# PCB.net
KiCad netlist of a schematic drawn in Altium Designer
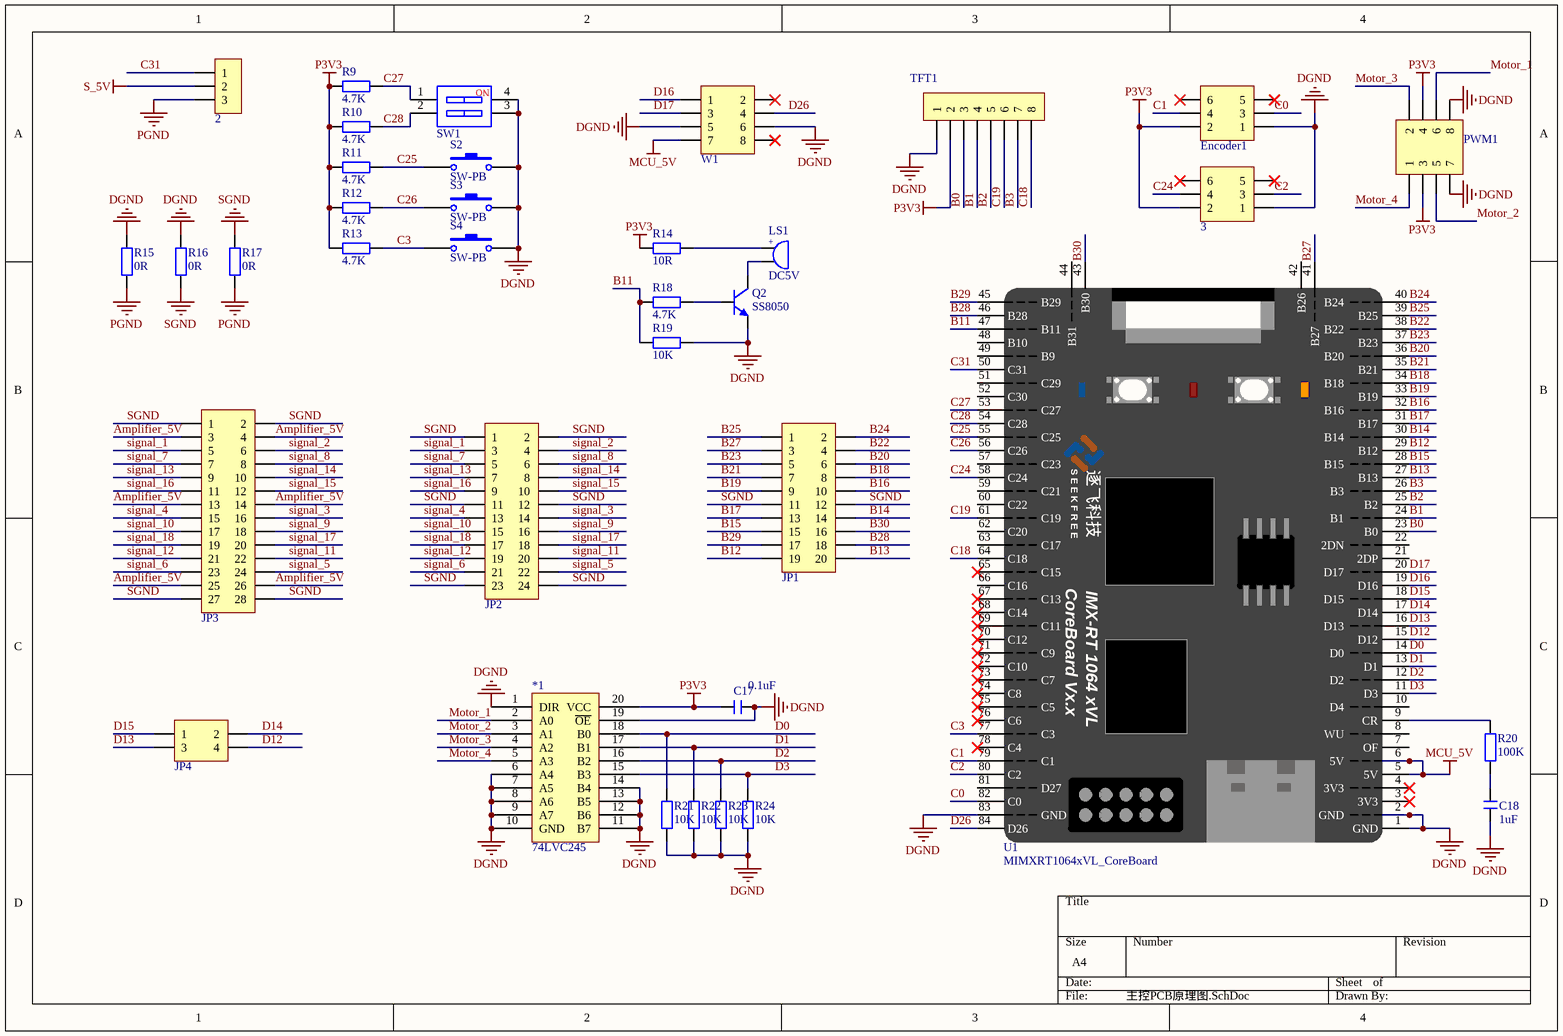
[diagram p0: 主控PCB原理图.SchDoc]

(export (version "E")
  (design (tool "Eeschema 10.0.6"))
  (components
    (comp (ref "*1")
      (value "74LVC245")
      (footprint "TSSOP20_M")
      (libsource (lib "主控PCB原理图库") (part "74LVC245"))
    )
    (comp (ref "2")
      (value "HDR-1X3")
      (footprint "HDR2.54-LI-3P")
      (description "3P接插件")
      (libsource (lib "5.4 - 接插件-脚距2.54 (100mil) ") (part "Header 3"))
    )
    (comp (ref "3")
      (value "Header3X2")
      (footprint "HDR2.54-LI-2x3P")
      (description "3*2P接插件")
      (libsource (lib "5.4 - 接插件-脚距2.54 (100mil) ") (part "Header 3X2"))
    )
    (comp (ref "C17")
      (value "0.1uF")
      (footprint "C 0603_L")
      (description "贴片电容")
      (libsource (lib "0.1 - 电阻-电容-电感") (part "C"))
    )
    (comp (ref "C18")
      (value "1uF")
      (footprint "C 0603_L")
      (description "贴片电容")
      (libsource (lib "0.1 - 电阻-电容-电感") (part "C"))
    )
    (comp (ref "Encoder1")
      (value "Header3X2")
      (footprint "HDR2.54-LI-2x3P")
      (description "3*2P接插件")
      (libsource (lib "5.4 - 接插件-脚距2.54 (100mil) ") (part "Header 3X2"))
    )
    (comp (ref "JP1")
      (value "Header 2X10")
      (footprint "HDR2.54-M-LS-2x10P")
      (description "10*2P接插件")
      (libsource (lib "5.4 - 接插件-脚距2.54 (100mil) ") (part "Header 10X2"))
    )
    (comp (ref "JP2")
      (value "Header 2X11")
      (footprint "HDR2.54-LI-2x12P")
      (description "12*2P接插件")
      (libsource (lib "5.4 - 接插件-脚距2.54 (100mil) ") (part "Header 12X2"))
    )
    (comp (ref "JP3")
      (value "Header 2X11")
      (footprint "HDR2.54-M-LS-2x14P")
      (description "14*2P接插件")
      (libsource (lib "5.4 - 接插件-脚距2.54 (100mil) ") (part "Header 14X2"))
    )
    (comp (ref "JP4")
      (value "Header2X2")
      (footprint "HDR2.54-LI-2x2P")
      (description "2*2P接插件")
      (libsource (lib "5.4 - 接插件-脚距2.54 (100mil) ") (part "Header 2X2"))
    )
    (comp (ref "LS1")
      (value "DC5V")
      (footprint "BEEP 7.6X12X9.5")
      (description "蜂鸣器")
      (libsource (lib "0.7 - 常用按键-开关-蜂鸣器-电池") (part "BEEP"))
    )
    (comp (ref "PWM1")
      (value "Header 4X2")
      (footprint "HDR2.54-LI-2x4P")
      (description "4*2P接插件")
      (libsource (lib "") (part "Header 4X2_1"))
    )
    (comp (ref "Q2")
      (value "SS8050")
      (footprint "SOT23-3N")
      (description "高频放大-NPN型")
      (libsource (lib "0.4 - 三极管-场效应管-可控硅") (part "8050-SMD"))
    )
    (comp (ref "R9")
      (value "4.7K")
      (footprint "R 0603_L")
      (description "贴片电阻")
      (libsource (lib "0.1 - 电阻-电容-电感") (part "R"))
    )
    (comp (ref "R10")
      (value "4.7K")
      (footprint "R 0603_L")
      (description "贴片电阻")
      (libsource (lib "0.1 - 电阻-电容-电感") (part "R"))
    )
    (comp (ref "R11")
      (value "4.7K")
      (footprint "R 0603_L")
      (description "贴片电阻")
      (libsource (lib "0.1 - 电阻-电容-电感") (part "R"))
    )
    (comp (ref "R12")
      (value "4.7K")
      (footprint "R 0603_L")
      (description "贴片电阻")
      (libsource (lib "0.1 - 电阻-电容-电感") (part "R"))
    )
    (comp (ref "R13")
      (value "4.7K")
      (footprint "R 0603_L")
      (description "贴片电阻")
      (libsource (lib "0.1 - 电阻-电容-电感") (part "R"))
    )
    (comp (ref "R14")
      (value "10R")
      (footprint "R 0603_L")
      (description "贴片电阻")
      (libsource (lib "0.1 - 电阻-电容-电感") (part "R"))
    )
    (comp (ref "R15")
      (value "0R")
      (footprint "R 0603_L")
      (description "贴片电阻")
      (libsource (lib "0.1 - 电阻-电容-电感") (part "R"))
    )
    (comp (ref "R16")
      (value "0R")
      (footprint "R 0603_L")
      (description "贴片电阻")
      (libsource (lib "0.1 - 电阻-电容-电感") (part "R"))
    )
    (comp (ref "R17")
      (value "0R")
      (footprint "R 0603_L")
      (description "贴片电阻")
      (libsource (lib "0.1 - 电阻-电容-电感") (part "R"))
    )
    (comp (ref "R18")
      (value "4.7K")
      (footprint "R 0603_L")
      (description "贴片电阻")
      (libsource (lib "0.1 - 电阻-电容-电感") (part "R"))
    )
    (comp (ref "R19")
      (value "10K")
      (footprint "R 0603_L")
      (description "贴片电阻")
      (libsource (lib "0.1 - 电阻-电容-电感") (part "R"))
    )
    (comp (ref "R20")
      (value "100K")
      (footprint "R 0603_L")
      (description "贴片电阻")
      (libsource (lib "0.1 - 电阻-电容-电感") (part "R"))
    )
    (comp (ref "R21")
      (value "10K")
      (footprint "R 0603_L")
      (description "贴片电阻")
      (libsource (lib "0.1 - 电阻-电容-电感") (part "R"))
    )
    (comp (ref "R22")
      (value "10K")
      (footprint "R 0603_L")
      (description "贴片电阻")
      (libsource (lib "0.1 - 电阻-电容-电感") (part "R"))
    )
    (comp (ref "R23")
      (value "10K")
      (footprint "R 0603_L")
      (description "贴片电阻")
      (libsource (lib "0.1 - 电阻-电容-电感") (part "R"))
    )
    (comp (ref "R24")
      (value "10K")
      (footprint "R 0603_L")
      (description "贴片电阻")
      (libsource (lib "0.1 - 电阻-电容-电感") (part "R"))
    )
    (comp (ref "S2")
      (value "SW-PB")
      (footprint "TSW SMD-3*6*4.3")
      (description "微动开关")
      (libsource (lib "0.7 - 常用按键-开关-蜂鸣器-电池") (part "SW-PB"))
    )
    (comp (ref "S3")
      (value "SW-PB")
      (footprint "TSW SMD-3*6*4.3")
      (description "微动开关")
      (libsource (lib "0.7 - 常用按键-开关-蜂鸣器-电池") (part "SW-PB"))
    )
    (comp (ref "S4")
      (value "SW-PB")
      (footprint "TSW SMD-3*6*4.3")
      (description "微动开关")
      (libsource (lib "0.7 - 常用按键-开关-蜂鸣器-电池") (part "SW-PB"))
    )
    (comp (ref "SW1")
      (value "SW-2P")
      (footprint "CSW DIP-2P_G")
      (description "2路编码开关")
      (libsource (lib "0.7 - 常用按键-开关-蜂鸣器-电池") (part "SW-2P"))
    )
    (comp (ref "TFT1")
      (value "HDR-1X8")
      (footprint "HDR2.54-LI-8P")
      (description "8P接插件")
      (libsource (lib "5.4 - 接插件-脚距2.54 (100mil) ") (part "Header 8"))
    )
    (comp (ref "U1")
      (value "MIMXRT1064xVL_CoreBoard")
      (footprint "MIMXRT1064xVL_CoreBoard")
      (description "逐飞科技i.MX RT1064核心板整体原理，可直接使用")
      (libsource (lib "RT1064 V1.2核心板原理库") (part "MIMXRT1064xVL_CoreBoard"))
    )
    (comp (ref "W1")
      (value "Header 4X2")
      (footprint "HDR2.54-M-LS-2x4P")
      (description "4*2P接插件")
      (libsource (lib "5.4 - 接插件-脚距2.54 (100mil) ") (part "Header 4X2"))
    )
  )
  (nets
    (net (code "1") (name "/Amplifier_5V") (class "Default")
      (node (ref "JP3") (pin "13") (pinfunction "13_13") (pintype "passive"))
      (node (ref "JP3") (pin "14") (pinfunction "14_14") (pintype "passive"))
      (node (ref "JP3") (pin "25") (pinfunction "25_25") (pintype "passive"))
      (node (ref "JP3") (pin "26") (pinfunction "26_26") (pintype "passive"))
      (node (ref "JP3") (pin "3") (pinfunction "3_3") (pintype "passive"))
      (node (ref "JP3") (pin "4") (pinfunction "4_4") (pintype "passive"))
    )
    (net (code "2") (name "/B0") (class "Default")
      (node (ref "TFT1") (pin "3") (pinfunction "3_3") (pintype "passive"))
      (node (ref "U1") (pin "23") (pinfunction "B0_23") (pintype "passive"))
    )
    (net (code "3") (name "/B1") (class "Default")
      (node (ref "TFT1") (pin "4") (pinfunction "4_4") (pintype "passive"))
      (node (ref "U1") (pin "24") (pinfunction "B1_24") (pintype "passive"))
    )
    (net (code "4") (name "/B2") (class "Default")
      (node (ref "TFT1") (pin "5") (pinfunction "5_5") (pintype "passive"))
      (node (ref "U1") (pin "25") (pinfunction "B2_25") (pintype "passive"))
    )
    (net (code "5") (name "/B3") (class "Default")
      (node (ref "TFT1") (pin "7") (pinfunction "7_7") (pintype "passive"))
      (node (ref "U1") (pin "26") (pinfunction "B3_26") (pintype "passive"))
    )
    (net (code "6") (name "/B11") (class "Default")
      (node (ref "R18") (pin "1") (pinfunction "1_1") (pintype "passive"))
      (node (ref "R19") (pin "1") (pinfunction "1_1") (pintype "passive"))
      (node (ref "U1") (pin "47") (pinfunction "B11_47") (pintype "passive"))
    )
    (net (code "7") (name "/B12") (class "Default")
      (node (ref "JP1") (pin "19") (pinfunction "19_19") (pintype "passive"))
      (node (ref "U1") (pin "29") (pinfunction "B12_29") (pintype "passive"))
    )
    (net (code "8") (name "/B13") (class "Default")
      (node (ref "JP1") (pin "20") (pinfunction "20_20") (pintype "passive"))
      (node (ref "U1") (pin "27") (pinfunction "B13_27") (pintype "passive"))
    )
    (net (code "9") (name "/B14") (class "Default")
      (node (ref "JP1") (pin "14") (pinfunction "14_14") (pintype "passive"))
      (node (ref "U1") (pin "30") (pinfunction "B14_30") (pintype "passive"))
    )
    (net (code "10") (name "/B15") (class "Default")
      (node (ref "JP1") (pin "15") (pinfunction "15_15") (pintype "passive"))
      (node (ref "U1") (pin "28") (pinfunction "B15_28") (pintype "passive"))
    )
    (net (code "11") (name "/B16") (class "Default")
      (node (ref "JP1") (pin "10") (pinfunction "10_10") (pintype "passive"))
      (node (ref "U1") (pin "32") (pinfunction "B16_32") (pintype "passive"))
    )
    (net (code "12") (name "/B17") (class "Default")
      (node (ref "JP1") (pin "13") (pinfunction "13_13") (pintype "passive"))
      (node (ref "U1") (pin "31") (pinfunction "B17_31") (pintype "passive"))
    )
    (net (code "13") (name "/B18") (class "Default")
      (node (ref "JP1") (pin "8") (pinfunction "8_8") (pintype "passive"))
      (node (ref "U1") (pin "34") (pinfunction "B18_34") (pintype "passive"))
    )
    (net (code "14") (name "/B19") (class "Default")
      (node (ref "JP1") (pin "9") (pinfunction "9_9") (pintype "passive"))
      (node (ref "U1") (pin "33") (pinfunction "B19_33") (pintype "passive"))
    )
    (net (code "15") (name "/B20") (class "Default")
      (node (ref "JP1") (pin "6") (pinfunction "6_6") (pintype "passive"))
      (node (ref "U1") (pin "36") (pinfunction "B20_36") (pintype "passive"))
    )
    (net (code "16") (name "/B21") (class "Default")
      (node (ref "JP1") (pin "7") (pinfunction "7_7") (pintype "passive"))
      (node (ref "U1") (pin "35") (pinfunction "B21_35") (pintype "passive"))
    )
    (net (code "17") (name "/B22") (class "Default")
      (node (ref "JP1") (pin "4") (pinfunction "4_4") (pintype "passive"))
      (node (ref "U1") (pin "38") (pinfunction "B22_38") (pintype "passive"))
    )
    (net (code "18") (name "/B23") (class "Default")
      (node (ref "JP1") (pin "5") (pinfunction "5_5") (pintype "passive"))
      (node (ref "U1") (pin "37") (pinfunction "B23_37") (pintype "passive"))
    )
    (net (code "19") (name "/B24") (class "Default")
      (node (ref "JP1") (pin "2") (pinfunction "2_2") (pintype "passive"))
      (node (ref "U1") (pin "40") (pinfunction "B24_40") (pintype "passive"))
    )
    (net (code "20") (name "/B25") (class "Default")
      (node (ref "JP1") (pin "1") (pinfunction "1_1") (pintype "passive"))
      (node (ref "U1") (pin "39") (pinfunction "B25_39") (pintype "passive"))
    )
    (net (code "21") (name "/B27") (class "Default")
      (node (ref "JP1") (pin "3") (pinfunction "3_3") (pintype "passive"))
      (node (ref "U1") (pin "41") (pinfunction "B27_41") (pintype "passive"))
    )
    (net (code "22") (name "/B28") (class "Default")
      (node (ref "JP1") (pin "18") (pinfunction "18_18") (pintype "passive"))
      (node (ref "U1") (pin "46") (pinfunction "B28_46") (pintype "passive"))
    )
    (net (code "23") (name "/B29") (class "Default")
      (node (ref "JP1") (pin "17") (pinfunction "17_17") (pintype "passive"))
      (node (ref "U1") (pin "45") (pinfunction "B29_45") (pintype "passive"))
    )
    (net (code "24") (name "/B30") (class "Default")
      (node (ref "JP1") (pin "16") (pinfunction "16_16") (pintype "passive"))
      (node (ref "U1") (pin "43") (pinfunction "B30_43") (pintype "passive"))
    )
    (net (code "25") (name "/C0") (class "Default")
      (node (ref "Encoder1") (pin "3") (pinfunction "3_3") (pintype "passive"))
      (node (ref "U1") (pin "82") (pinfunction "C0_82") (pintype "passive"))
    )
    (net (code "26") (name "/C1") (class "Default")
      (node (ref "Encoder1") (pin "4") (pinfunction "4_4") (pintype "passive"))
      (node (ref "U1") (pin "79") (pinfunction "C1_79") (pintype "passive"))
    )
    (net (code "27") (name "/C2") (class "Default")
      (node (ref "3") (pin "3") (pinfunction "3_3") (pintype "passive"))
      (node (ref "U1") (pin "80") (pinfunction "C2_80") (pintype "passive"))
    )
    (net (code "28") (name "/C3") (class "Default")
      (node (ref "R13") (pin "2") (pinfunction "2_2") (pintype "passive"))
      (node (ref "S4") (pin "1") (pinfunction "1_1") (pintype "passive"))
      (node (ref "U1") (pin "77") (pinfunction "C3_77") (pintype "passive"))
    )
    (net (code "29") (name "/C18") (class "Default")
      (node (ref "TFT1") (pin "8") (pinfunction "8_8") (pintype "passive"))
      (node (ref "U1") (pin "64") (pinfunction "C18_64") (pintype "passive"))
    )
    (net (code "30") (name "/C19") (class "Default")
      (node (ref "TFT1") (pin "6") (pinfunction "6_6") (pintype "passive"))
      (node (ref "U1") (pin "61") (pinfunction "C19_61") (pintype "passive"))
    )
    (net (code "31") (name "/C24") (class "Default")
      (node (ref "3") (pin "4") (pinfunction "4_4") (pintype "passive"))
      (node (ref "U1") (pin "58") (pinfunction "C24_58") (pintype "passive"))
    )
    (net (code "32") (name "/C25") (class "Default")
      (node (ref "R11") (pin "2") (pinfunction "2_2") (pintype "passive"))
      (node (ref "S2") (pin "1") (pinfunction "1_1") (pintype "passive"))
      (node (ref "U1") (pin "55") (pinfunction "C25_55") (pintype "passive"))
    )
    (net (code "33") (name "/C26") (class "Default")
      (node (ref "R12") (pin "2") (pinfunction "2_2") (pintype "passive"))
      (node (ref "S3") (pin "1") (pinfunction "1_1") (pintype "passive"))
      (node (ref "U1") (pin "56") (pinfunction "C26_56") (pintype "passive"))
    )
    (net (code "34") (name "/C27") (class "Default")
      (node (ref "R9") (pin "2") (pinfunction "2_2") (pintype "passive"))
      (node (ref "SW1") (pin "1") (pinfunction "1_1") (pintype "passive"))
      (node (ref "U1") (pin "53") (pinfunction "C27_53") (pintype "passive"))
    )
    (net (code "35") (name "/C28") (class "Default")
      (node (ref "R10") (pin "2") (pinfunction "2_2") (pintype "passive"))
      (node (ref "SW1") (pin "2") (pinfunction "2_2") (pintype "passive"))
      (node (ref "U1") (pin "54") (pinfunction "C28_54") (pintype "passive"))
    )
    (net (code "36") (name "/C31") (class "Default")
      (node (ref "2") (pin "1") (pinfunction "1_1") (pintype "passive"))
      (node (ref "U1") (pin "50") (pinfunction "C31_50") (pintype "passive"))
    )
    (net (code "37") (name "/D0") (class "Default")
      (node (ref "*1") (pin "18") (pinfunction "B0_18") (pintype "passive"))
      (node (ref "R21") (pin "2") (pinfunction "2_2") (pintype "passive"))
      (node (ref "U1") (pin "14") (pinfunction "D0_14") (pintype "passive"))
    )
    (net (code "38") (name "/D1") (class "Default")
      (node (ref "*1") (pin "17") (pinfunction "B1_17") (pintype "passive"))
      (node (ref "R22") (pin "2") (pinfunction "2_2") (pintype "passive"))
      (node (ref "U1") (pin "13") (pinfunction "D1_13") (pintype "passive"))
    )
    (net (code "39") (name "/D2") (class "Default")
      (node (ref "*1") (pin "16") (pinfunction "B2_16") (pintype "passive"))
      (node (ref "R23") (pin "2") (pinfunction "2_2") (pintype "passive"))
      (node (ref "U1") (pin "12") (pinfunction "D2_12") (pintype "passive"))
    )
    (net (code "40") (name "/D3") (class "Default")
      (node (ref "*1") (pin "15") (pinfunction "B3_15") (pintype "passive"))
      (node (ref "R24") (pin "2") (pinfunction "2_2") (pintype "passive"))
      (node (ref "U1") (pin "11") (pinfunction "D3_11") (pintype "passive"))
    )
    (net (code "41") (name "/D12") (class "Default")
      (node (ref "JP4") (pin "4") (pinfunction "4_4") (pintype "passive"))
      (node (ref "U1") (pin "15") (pinfunction "D12_15") (pintype "passive"))
    )
    (net (code "42") (name "/D13") (class "Default")
      (node (ref "JP4") (pin "3") (pinfunction "3_3") (pintype "passive"))
      (node (ref "U1") (pin "16") (pinfunction "D13_16") (pintype "passive"))
    )
    (net (code "43") (name "/D14") (class "Default")
      (node (ref "JP4") (pin "2") (pinfunction "2_2") (pintype "passive"))
      (node (ref "U1") (pin "17") (pinfunction "D14_17") (pintype "passive"))
    )
    (net (code "44") (name "/D15") (class "Default")
      (node (ref "JP4") (pin "1") (pinfunction "1_1") (pintype "passive"))
      (node (ref "U1") (pin "18") (pinfunction "D15_18") (pintype "passive"))
    )
    (net (code "45") (name "/D16") (class "Default")
      (node (ref "U1") (pin "19") (pinfunction "D16_19") (pintype "passive"))
      (node (ref "W1") (pin "1") (pinfunction "1_1") (pintype "passive"))
    )
    (net (code "46") (name "/D17") (class "Default")
      (node (ref "U1") (pin "20") (pinfunction "D17_20") (pintype "passive"))
      (node (ref "W1") (pin "3") (pinfunction "3_3") (pintype "passive"))
    )
    (net (code "47") (name "/D26") (class "Default")
      (node (ref "U1") (pin "84") (pinfunction "D26_84") (pintype "passive"))
      (node (ref "W1") (pin "4") (pinfunction "4_4") (pintype "passive"))
    )
    (net (code "48") (name "/Motor_1") (class "Default")
      (node (ref "*1") (pin "2") (pinfunction "A0_2") (pintype "passive"))
      (node (ref "PWM1") (pin "6") (pinfunction "6_6") (pintype "passive"))
    )
    (net (code "49") (name "/Motor_2") (class "Default")
      (node (ref "*1") (pin "3") (pinfunction "A1_3") (pintype "passive"))
      (node (ref "PWM1") (pin "5") (pinfunction "5_5") (pintype "passive"))
    )
    (net (code "50") (name "/Motor_3") (class "Default")
      (node (ref "*1") (pin "4") (pinfunction "A2_4") (pintype "passive"))
      (node (ref "PWM1") (pin "2") (pinfunction "2_2") (pintype "passive"))
    )
    (net (code "51") (name "/Motor_4") (class "Default")
      (node (ref "*1") (pin "5") (pinfunction "A3_5") (pintype "passive"))
      (node (ref "PWM1") (pin "1") (pinfunction "1_1") (pintype "passive"))
    )
    (net (code "52") (name "/signal_1") (class "Default")
      (node (ref "JP2") (pin "3") (pinfunction "3_3") (pintype "passive"))
      (node (ref "JP3") (pin "5") (pinfunction "5_5") (pintype "passive"))
    )
    (net (code "53") (name "/signal_2") (class "Default")
      (node (ref "JP2") (pin "4") (pinfunction "4_4") (pintype "passive"))
      (node (ref "JP3") (pin "6") (pinfunction "6_6") (pintype "passive"))
    )
    (net (code "54") (name "/signal_3") (class "Default")
      (node (ref "JP2") (pin "14") (pinfunction "14_14") (pintype "passive"))
      (node (ref "JP3") (pin "16") (pinfunction "16_16") (pintype "passive"))
    )
    (net (code "55") (name "/signal_4") (class "Default")
      (node (ref "JP2") (pin "13") (pinfunction "13_13") (pintype "passive"))
      (node (ref "JP3") (pin "15") (pinfunction "15_15") (pintype "passive"))
    )
    (net (code "56") (name "/signal_5") (class "Default")
      (node (ref "JP2") (pin "22") (pinfunction "22_22") (pintype "passive"))
      (node (ref "JP3") (pin "24") (pinfunction "24_24") (pintype "passive"))
    )
    (net (code "57") (name "/signal_6") (class "Default")
      (node (ref "JP2") (pin "21") (pinfunction "21_21") (pintype "passive"))
      (node (ref "JP3") (pin "23") (pinfunction "23_23") (pintype "passive"))
    )
    (net (code "58") (name "/signal_7") (class "Default")
      (node (ref "JP2") (pin "5") (pinfunction "5_5") (pintype "passive"))
      (node (ref "JP3") (pin "7") (pinfunction "7_7") (pintype "passive"))
    )
    (net (code "59") (name "/signal_8") (class "Default")
      (node (ref "JP2") (pin "6") (pinfunction "6_6") (pintype "passive"))
      (node (ref "JP3") (pin "8") (pinfunction "8_8") (pintype "passive"))
    )
    (net (code "60") (name "/signal_9") (class "Default")
      (node (ref "JP2") (pin "16") (pinfunction "16_16") (pintype "passive"))
      (node (ref "JP3") (pin "18") (pinfunction "18_18") (pintype "passive"))
    )
    (net (code "61") (name "/signal_10") (class "Default")
      (node (ref "JP2") (pin "15") (pinfunction "15_15") (pintype "passive"))
      (node (ref "JP3") (pin "17") (pinfunction "17_17") (pintype "passive"))
    )
    (net (code "62") (name "/signal_11") (class "Default")
      (node (ref "JP2") (pin "20") (pinfunction "20_20") (pintype "passive"))
      (node (ref "JP3") (pin "22") (pinfunction "22_22") (pintype "passive"))
    )
    (net (code "63") (name "/signal_12") (class "Default")
      (node (ref "JP2") (pin "19") (pinfunction "19_19") (pintype "passive"))
      (node (ref "JP3") (pin "21") (pinfunction "21_21") (pintype "passive"))
    )
    (net (code "64") (name "/signal_13") (class "Default")
      (node (ref "JP2") (pin "7") (pinfunction "7_7") (pintype "passive"))
      (node (ref "JP3") (pin "9") (pinfunction "9_9") (pintype "passive"))
    )
    (net (code "65") (name "/signal_14") (class "Default")
      (node (ref "JP2") (pin "8") (pinfunction "8_8") (pintype "passive"))
      (node (ref "JP3") (pin "10") (pinfunction "10_10") (pintype "passive"))
    )
    (net (code "66") (name "/signal_15") (class "Default")
      (node (ref "JP2") (pin "10") (pinfunction "10_10") (pintype "passive"))
      (node (ref "JP3") (pin "12") (pinfunction "12_12") (pintype "passive"))
    )
    (net (code "67") (name "/signal_16") (class "Default")
      (node (ref "JP2") (pin "9") (pinfunction "9_9") (pintype "passive"))
      (node (ref "JP3") (pin "11") (pinfunction "11_11") (pintype "passive"))
    )
    (net (code "68") (name "/signal_17") (class "Default")
      (node (ref "JP2") (pin "18") (pinfunction "18_18") (pintype "passive"))
      (node (ref "JP3") (pin "20") (pinfunction "20_20") (pintype "passive"))
    )
    (net (code "69") (name "/signal_18") (class "Default")
      (node (ref "JP2") (pin "17") (pinfunction "17_17") (pintype "passive"))
      (node (ref "JP3") (pin "19") (pinfunction "19_19") (pintype "passive"))
    )
    (net (code "70") (name "DGND") (class "Default")
      (node (ref "*1") (pin "1") (pinfunction "DIR_1") (pintype "passive"))
      (node (ref "*1") (pin "10") (pinfunction "GND_10") (pintype "passive"))
      (node (ref "*1") (pin "11") (pinfunction "B7_11") (pintype "passive"))
      (node (ref "*1") (pin "12") (pinfunction "B6_12") (pintype "passive"))
      (node (ref "*1") (pin "13") (pinfunction "B5_13") (pintype "passive"))
      (node (ref "*1") (pin "14") (pinfunction "B4_14") (pintype "passive"))
      (node (ref "*1") (pin "19") (pinfunction "~{OE}_19") (pintype "passive"))
      (node (ref "*1") (pin "6") (pinfunction "A4_6") (pintype "passive"))
      (node (ref "*1") (pin "7") (pinfunction "A5_7") (pintype "passive"))
      (node (ref "*1") (pin "8") (pinfunction "A6_8") (pintype "passive"))
      (node (ref "*1") (pin "9") (pinfunction "A7_9") (pintype "passive"))
      (node (ref "3") (pin "1") (pinfunction "1_1") (pintype "passive"))
      (node (ref "C17") (pin "2") (pinfunction "2_2") (pintype "passive"))
      (node (ref "C18") (pin "1") (pinfunction "1_1") (pintype "passive"))
      (node (ref "Encoder1") (pin "1") (pinfunction "1_1") (pintype "passive"))
      (node (ref "PWM1") (pin "7") (pinfunction "7_7") (pintype "passive"))
      (node (ref "PWM1") (pin "8") (pinfunction "8_8") (pintype "passive"))
      (node (ref "Q2") (pin "2") (pinfunction "E_2") (pintype "passive"))
      (node (ref "R15") (pin "2") (pinfunction "2_2") (pintype "passive"))
      (node (ref "R16") (pin "2") (pinfunction "2_2") (pintype "passive"))
      (node (ref "R19") (pin "2") (pinfunction "2_2") (pintype "passive"))
      (node (ref "R21") (pin "1") (pinfunction "1_1") (pintype "passive"))
      (node (ref "R22") (pin "1") (pinfunction "1_1") (pintype "passive"))
      (node (ref "R23") (pin "1") (pinfunction "1_1") (pintype "passive"))
      (node (ref "R24") (pin "1") (pinfunction "1_1") (pintype "passive"))
      (node (ref "S2") (pin "2") (pinfunction "2_2") (pintype "passive"))
      (node (ref "S3") (pin "2") (pinfunction "2_2") (pintype "passive"))
      (node (ref "S4") (pin "2") (pinfunction "2_2") (pintype "passive"))
      (node (ref "SW1") (pin "3") (pinfunction "3_3") (pintype "passive"))
      (node (ref "SW1") (pin "4") (pinfunction "4_4") (pintype "passive"))
      (node (ref "TFT1") (pin "1") (pinfunction "1_1") (pintype "passive"))
      (node (ref "U1") (pin "1") (pinfunction "GND_1") (pintype "passive"))
      (node (ref "U1") (pin "2") (pinfunction "GND_2") (pintype "passive"))
      (node (ref "U1") (pin "83") (pinfunction "GND_83") (pintype "passive"))
      (node (ref "W1") (pin "5") (pinfunction "5_5") (pintype "passive"))
      (node (ref "W1") (pin "6") (pinfunction "6_6") (pintype "passive"))
    )
    (net (code "71") (name "MCU_5V") (class "Default")
      (node (ref "U1") (pin "5") (pinfunction "5V_5") (pintype "passive"))
      (node (ref "U1") (pin "6") (pinfunction "5V_6") (pintype "passive"))
      (node (ref "W1") (pin "7") (pinfunction "7_7") (pintype "passive"))
    )
    (net (code "72") (name "Net-(C18-Pad2)") (class "Default")
      (node (ref "C18") (pin "2") (pinfunction "2_2") (pintype "passive"))
      (node (ref "R20") (pin "1") (pinfunction "1_1") (pintype "passive"))
    )
    (net (code "73") (name "Net-(LS1-Pad1)") (class "Default")
      (node (ref "LS1") (pin "1") (pinfunction "1_1") (pintype "passive"))
      (node (ref "R14") (pin "2") (pinfunction "2_2") (pintype "passive"))
    )
    (net (code "74") (name "Net-(Q2-B)") (class "Default")
      (node (ref "Q2") (pin "1") (pinfunction "B_1") (pintype "passive"))
      (node (ref "R18") (pin "2") (pinfunction "2_2") (pintype "passive"))
    )
    (net (code "75") (name "Net-(Q2-C)") (class "Default")
      (node (ref "LS1") (pin "2") (pinfunction "2_2") (pintype "passive"))
      (node (ref "Q2") (pin "3") (pinfunction "C_3") (pintype "passive"))
    )
    (net (code "76") (name "Net-(U1-CR)") (class "Default")
      (node (ref "R20") (pin "2") (pinfunction "2_2") (pintype "passive"))
      (node (ref "U1") (pin "9") (pinfunction "CR_9") (pintype "passive"))
    )
    (net (code "77") (name "P3V3") (class "Default")
      (node (ref "*1") (pin "20") (pinfunction "VCC_20") (pintype "passive"))
      (node (ref "3") (pin "2") (pinfunction "2_2") (pintype "passive"))
      (node (ref "C17") (pin "1") (pinfunction "1_1") (pintype "passive"))
      (node (ref "Encoder1") (pin "2") (pinfunction "2_2") (pintype "passive"))
      (node (ref "PWM1") (pin "3") (pinfunction "3_3") (pintype "passive"))
      (node (ref "PWM1") (pin "4") (pinfunction "4_4") (pintype "passive"))
      (node (ref "R10") (pin "1") (pinfunction "1_1") (pintype "passive"))
      (node (ref "R11") (pin "1") (pinfunction "1_1") (pintype "passive"))
      (node (ref "R12") (pin "1") (pinfunction "1_1") (pintype "passive"))
      (node (ref "R13") (pin "1") (pinfunction "1_1") (pintype "passive"))
      (node (ref "R14") (pin "1") (pinfunction "1_1") (pintype "passive"))
      (node (ref "R9") (pin "1") (pinfunction "1_1") (pintype "passive"))
      (node (ref "TFT1") (pin "2") (pinfunction "2_2") (pintype "passive"))
    )
    (net (code "78") (name "PGND") (class "Default")
      (node (ref "2") (pin "3") (pinfunction "3_3") (pintype "passive"))
      (node (ref "R15") (pin "1") (pinfunction "1_1") (pintype "passive"))
      (node (ref "R17") (pin "1") (pinfunction "1_1") (pintype "passive"))
    )
    (net (code "79") (name "SGND") (class "Default")
      (node (ref "JP1") (pin "11") (pinfunction "11_11") (pintype "passive"))
      (node (ref "JP1") (pin "12") (pinfunction "12_12") (pintype "passive"))
      (node (ref "JP2") (pin "1") (pinfunction "1_1") (pintype "passive"))
      (node (ref "JP2") (pin "11") (pinfunction "11_11") (pintype "passive"))
      (node (ref "JP2") (pin "12") (pinfunction "12_12") (pintype "passive"))
      (node (ref "JP2") (pin "2") (pinfunction "2_2") (pintype "passive"))
      (node (ref "JP2") (pin "23") (pinfunction "23_23") (pintype "passive"))
      (node (ref "JP2") (pin "24") (pinfunction "24_24") (pintype "passive"))
      (node (ref "JP3") (pin "1") (pinfunction "1_1") (pintype "passive"))
      (node (ref "JP3") (pin "2") (pinfunction "2_2") (pintype "passive"))
      (node (ref "JP3") (pin "27") (pinfunction "27_27") (pintype "passive"))
      (node (ref "JP3") (pin "28") (pinfunction "28_28") (pintype "passive"))
      (node (ref "R16") (pin "1") (pinfunction "1_1") (pintype "passive"))
      (node (ref "R17") (pin "2") (pinfunction "2_2") (pintype "passive"))
    )
    (net (code "80") (name "S_5V") (class "Default")
      (node (ref "2") (pin "2") (pinfunction "2_2") (pintype "passive"))
    )
    (net (code "81") (name "unconnected-(3-Pad5)") (class "Default")
      (node (ref "3") (pin "5") (pinfunction "5_5") (pintype "passive+no_connect"))
    )
    (net (code "82") (name "unconnected-(3-Pad6)") (class "Default")
      (node (ref "3") (pin "6") (pinfunction "6_6") (pintype "passive+no_connect"))
    )
    (net (code "83") (name "unconnected-(Encoder1-Pad5)") (class "Default")
      (node (ref "Encoder1") (pin "5") (pinfunction "5_5") (pintype "passive+no_connect"))
    )
    (net (code "84") (name "unconnected-(Encoder1-Pad6)") (class "Default")
      (node (ref "Encoder1") (pin "6") (pinfunction "6_6") (pintype "passive+no_connect"))
    )
    (net (code "85") (name "unconnected-(U1-2DN-Pad22)") (class "Default")
      (node (ref "U1") (pin "22") (pinfunction "2DN_22") (pintype "passive"))
    )
    (net (code "86") (name "unconnected-(U1-2DP-Pad21)") (class "Default")
      (node (ref "U1") (pin "21") (pinfunction "2DP_21") (pintype "passive"))
    )
    (net (code "87") (name "unconnected-(U1-3V3-Pad3)") (class "Default")
      (node (ref "U1") (pin "3") (pinfunction "3V3_3") (pintype "passive+no_connect"))
    )
    (net (code "88") (name "unconnected-(U1-3V3-Pad4)") (class "Default")
      (node (ref "U1") (pin "4") (pinfunction "3V3_4") (pintype "passive+no_connect"))
    )
    (net (code "89") (name "unconnected-(U1-B9-Pad49)") (class "Default")
      (node (ref "U1") (pin "49") (pinfunction "B9_49") (pintype "passive"))
    )
    (net (code "90") (name "unconnected-(U1-B10-Pad48)") (class "Default")
      (node (ref "U1") (pin "48") (pinfunction "B10_48") (pintype "passive"))
    )
    (net (code "91") (name "unconnected-(U1-B26-Pad42)") (class "Default")
      (node (ref "U1") (pin "42") (pinfunction "B26_42") (pintype "passive"))
    )
    (net (code "92") (name "unconnected-(U1-B31-Pad44)") (class "Default")
      (node (ref "U1") (pin "44") (pinfunction "B31_44") (pintype "passive"))
    )
    (net (code "93") (name "unconnected-(U1-C4-Pad78)") (class "Default")
      (node (ref "U1") (pin "78") (pinfunction "C4_78") (pintype "passive+no_connect"))
    )
    (net (code "94") (name "unconnected-(U1-C5-Pad75)") (class "Default")
      (node (ref "U1") (pin "75") (pinfunction "C5_75") (pintype "passive+no_connect"))
    )
    (net (code "95") (name "unconnected-(U1-C6-Pad76)") (class "Default")
      (node (ref "U1") (pin "76") (pinfunction "C6_76") (pintype "passive+no_connect"))
    )
    (net (code "96") (name "unconnected-(U1-C7-Pad73)") (class "Default")
      (node (ref "U1") (pin "73") (pinfunction "C7_73") (pintype "passive+no_connect"))
    )
    (net (code "97") (name "unconnected-(U1-C8-Pad74)") (class "Default")
      (node (ref "U1") (pin "74") (pinfunction "C8_74") (pintype "passive+no_connect"))
    )
    (net (code "98") (name "unconnected-(U1-C9-Pad71)") (class "Default")
      (node (ref "U1") (pin "71") (pinfunction "C9_71") (pintype "passive+no_connect"))
    )
    (net (code "99") (name "unconnected-(U1-C10-Pad72)") (class "Default")
      (node (ref "U1") (pin "72") (pinfunction "C10_72") (pintype "passive+no_connect"))
    )
    (net (code "100") (name "unconnected-(U1-C11-Pad69)") (class "Default")
      (node (ref "U1") (pin "69") (pinfunction "C11_69") (pintype "passive+no_connect"))
    )
    (net (code "101") (name "unconnected-(U1-C12-Pad70)") (class "Default")
      (node (ref "U1") (pin "70") (pinfunction "C12_70") (pintype "passive+no_connect"))
    )
    (net (code "102") (name "unconnected-(U1-C13-Pad67)") (class "Default")
      (node (ref "U1") (pin "67") (pinfunction "C13_67") (pintype "passive+no_connect"))
    )
    (net (code "103") (name "unconnected-(U1-C14-Pad68)") (class "Default")
      (node (ref "U1") (pin "68") (pinfunction "C14_68") (pintype "passive+no_connect"))
    )
    (net (code "104") (name "unconnected-(U1-C15-Pad65)") (class "Default")
      (node (ref "U1") (pin "65") (pinfunction "C15_65") (pintype "passive+no_connect"))
    )
    (net (code "105") (name "unconnected-(U1-C16-Pad66)") (class "Default")
      (node (ref "U1") (pin "66") (pinfunction "C16_66") (pintype "passive"))
    )
    (net (code "106") (name "unconnected-(U1-C17-Pad63)") (class "Default")
      (node (ref "U1") (pin "63") (pinfunction "C17_63") (pintype "passive"))
    )
    (net (code "107") (name "unconnected-(U1-C20-Pad62)") (class "Default")
      (node (ref "U1") (pin "62") (pinfunction "C20_62") (pintype "passive"))
    )
    (net (code "108") (name "unconnected-(U1-C21-Pad59)") (class "Default")
      (node (ref "U1") (pin "59") (pinfunction "C21_59") (pintype "passive"))
    )
    (net (code "109") (name "unconnected-(U1-C22-Pad60)") (class "Default")
      (node (ref "U1") (pin "60") (pinfunction "C22_60") (pintype "passive"))
    )
    (net (code "110") (name "unconnected-(U1-C23-Pad57)") (class "Default")
      (node (ref "U1") (pin "57") (pinfunction "C23_57") (pintype "passive"))
    )
    (net (code "111") (name "unconnected-(U1-C29-Pad51)") (class "Default")
      (node (ref "U1") (pin "51") (pinfunction "C29_51") (pintype "passive"))
    )
    (net (code "112") (name "unconnected-(U1-C30-Pad52)") (class "Default")
      (node (ref "U1") (pin "52") (pinfunction "C30_52") (pintype "passive"))
    )
    (net (code "113") (name "unconnected-(U1-D4-Pad10)") (class "Default")
      (node (ref "U1") (pin "10") (pinfunction "D4_10") (pintype "passive"))
    )
    (net (code "114") (name "unconnected-(U1-D27-Pad81)") (class "Default")
      (node (ref "U1") (pin "81") (pinfunction "D27_81") (pintype "passive"))
    )
    (net (code "115") (name "unconnected-(U1-OF-Pad7)") (class "Default")
      (node (ref "U1") (pin "7") (pinfunction "OF_7") (pintype "passive"))
    )
    (net (code "116") (name "unconnected-(U1-WU-Pad8)") (class "Default")
      (node (ref "U1") (pin "8") (pinfunction "WU_8") (pintype "passive"))
    )
    (net (code "117") (name "unconnected-(W1-Pad2)") (class "Default")
      (node (ref "W1") (pin "2") (pinfunction "2_2") (pintype "passive+no_connect"))
    )
    (net (code "118") (name "unconnected-(W1-Pad8)") (class "Default")
      (node (ref "W1") (pin "8") (pinfunction "8_8") (pintype "passive+no_connect"))
    )
  )
)
